# 1U_attenuvert_redesign.net
KiCad netlist of a schematic drawn in EAGLE
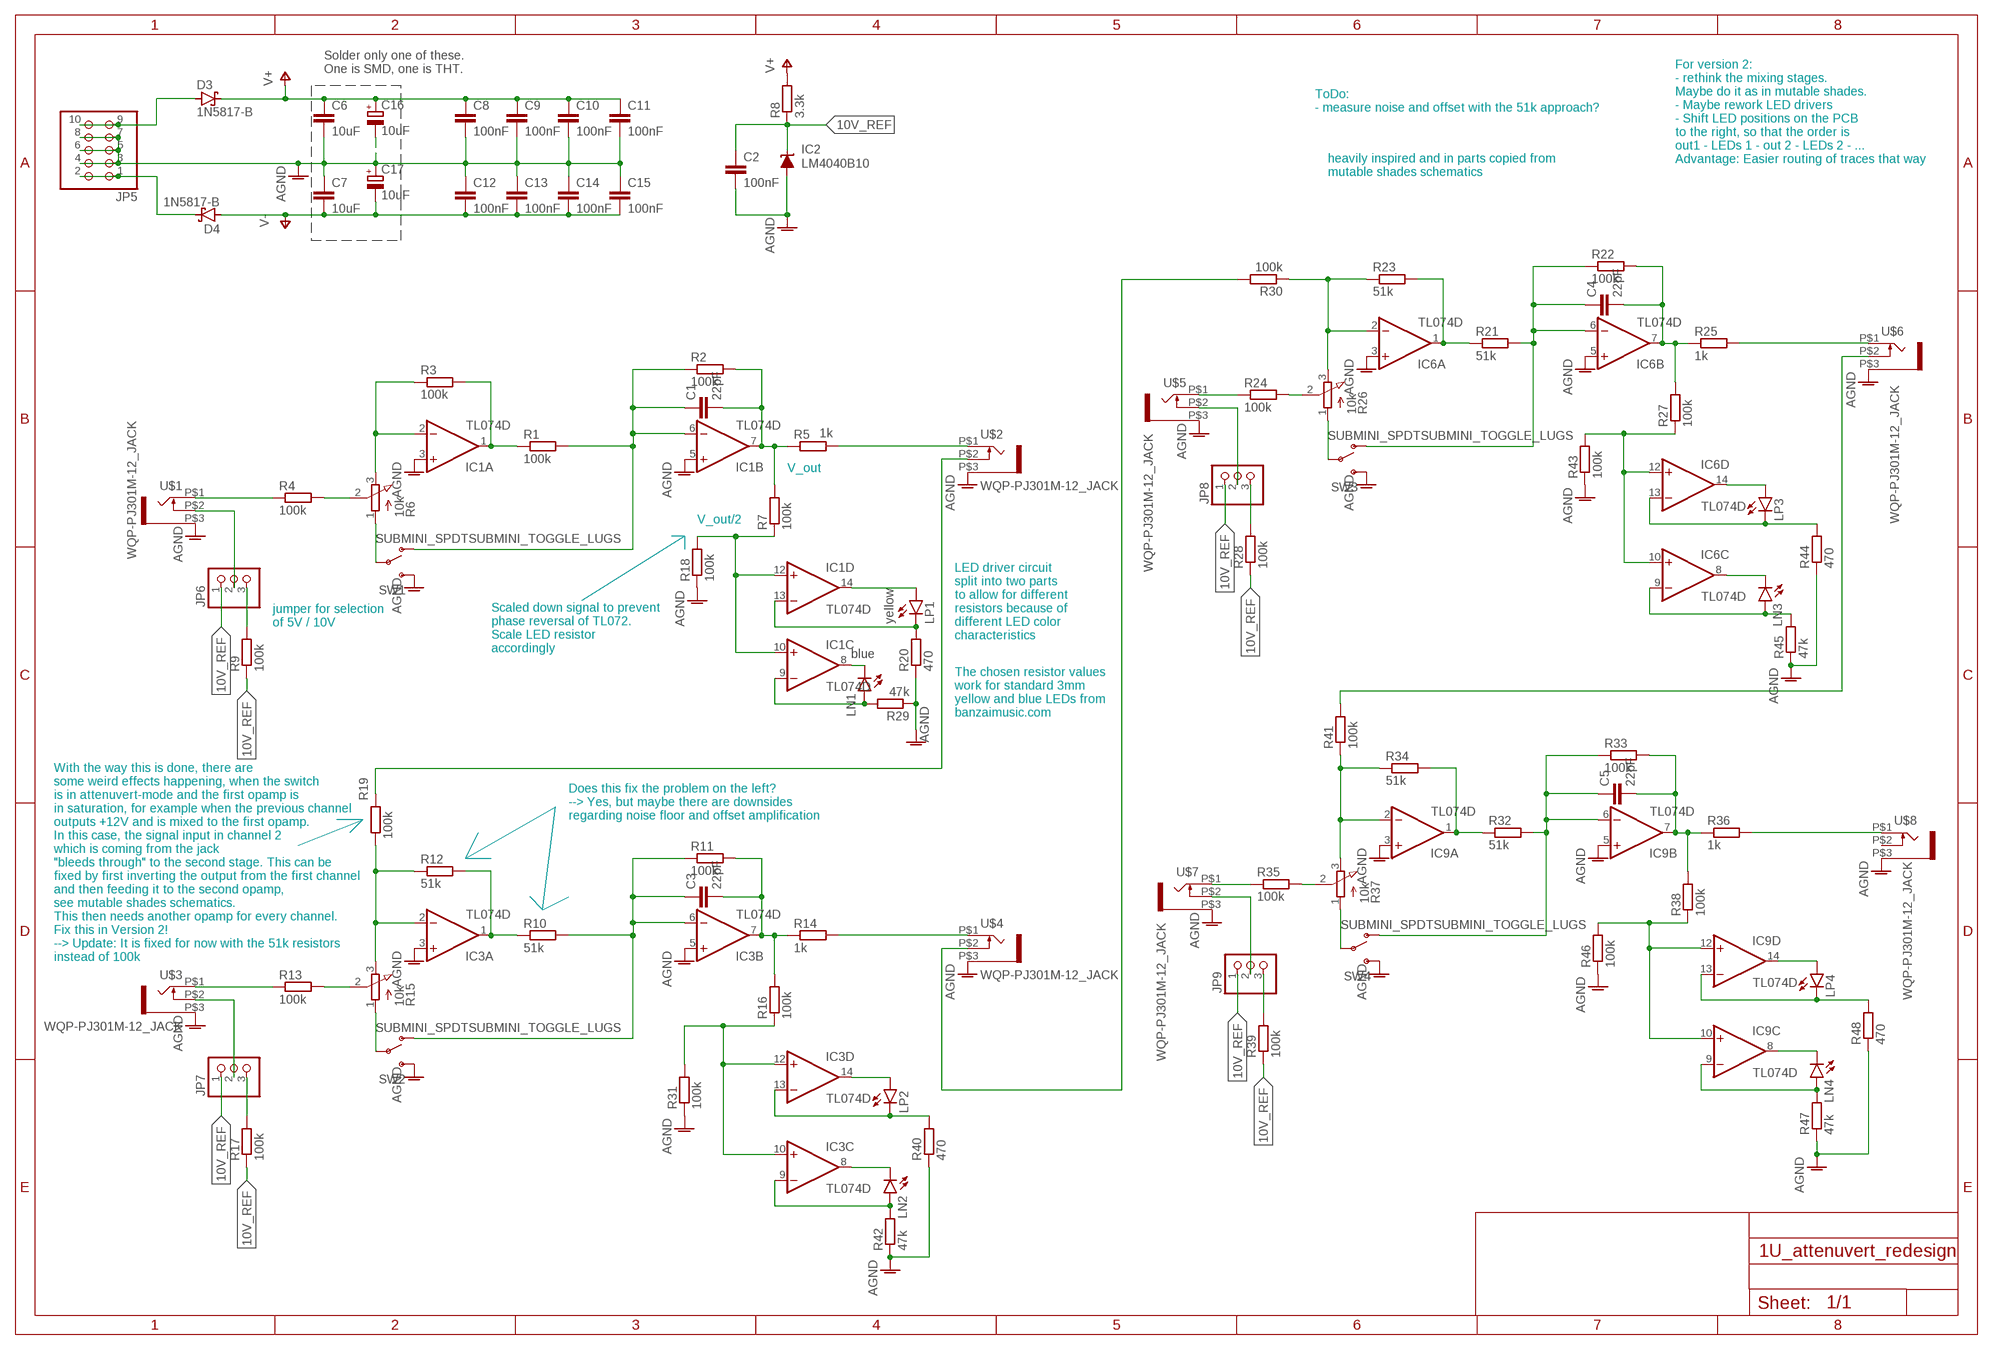
[diagram p0: schematic, sheet 1]

(export (version "E")
  (design (tool "Eeschema 10.0.6"))
  (components
    (comp (ref "C1")
      (value "22pF")
      (footprint "eagle-import:C0603")
      (libsource (lib "eagle-import") (part "C-EUC0603"))
    )
    (comp (ref "C2")
      (value "100nF")
      (footprint "eagle-import:C0603")
      (libsource (lib "eagle-import") (part "C-EUC0603"))
    )
    (comp (ref "C3")
      (value "22pF")
      (footprint "eagle-import:C0603")
      (libsource (lib "eagle-import") (part "C-EUC0603"))
    )
    (comp (ref "C4")
      (value "22pF")
      (footprint "eagle-import:C0603")
      (libsource (lib "eagle-import") (part "C-EUC0603"))
    )
    (comp (ref "C5")
      (value "22pF")
      (footprint "eagle-import:C0603")
      (libsource (lib "eagle-import") (part "C-EUC0603"))
    )
    (comp (ref "C6")
      (value "10uF")
      (footprint "eagle-import:C0805")
      (libsource (lib "eagle-import") (part "C-EUC0805"))
    )
    (comp (ref "C7")
      (value "10uF")
      (footprint "eagle-import:C0805")
      (libsource (lib "eagle-import") (part "C-EUC0805"))
    )
    (comp (ref "C8")
      (value "100nF")
      (footprint "eagle-import:C0603")
      (libsource (lib "eagle-import") (part "C-EUC0603"))
    )
    (comp (ref "C9")
      (value "100nF")
      (footprint "eagle-import:C0603")
      (libsource (lib "eagle-import") (part "C-EUC0603"))
    )
    (comp (ref "C10")
      (value "100nF")
      (footprint "eagle-import:C0603")
      (libsource (lib "eagle-import") (part "C-EUC0603"))
    )
    (comp (ref "C11")
      (value "100nF")
      (footprint "eagle-import:C0603")
      (libsource (lib "eagle-import") (part "C-EUC0603"))
    )
    (comp (ref "C12")
      (value "100nF")
      (footprint "eagle-import:C0603")
      (libsource (lib "eagle-import") (part "C-EUC0603"))
    )
    (comp (ref "C13")
      (value "100nF")
      (footprint "eagle-import:C0603")
      (libsource (lib "eagle-import") (part "C-EUC0603"))
    )
    (comp (ref "C14")
      (value "100nF")
      (footprint "eagle-import:C0603")
      (libsource (lib "eagle-import") (part "C-EUC0603"))
    )
    (comp (ref "C15")
      (value "100nF")
      (footprint "eagle-import:C0603")
      (libsource (lib "eagle-import") (part "C-EUC0603"))
    )
    (comp (ref "C16")
      (value "10uF")
      (footprint "eagle-import:E2,5-6")
      (libsource (lib "eagle-import") (part "CPOL-EUE2.5-6"))
    )
    (comp (ref "C17")
      (value "10uF")
      (footprint "eagle-import:E2,5-6")
      (libsource (lib "eagle-import") (part "CPOL-EUE2.5-6"))
    )
    (comp (ref "D3")
      (value "1N5817-B")
      (footprint "eagle-import:DO41-7.6")
      (libsource (lib "eagle-import") (part "1N5817-B"))
    )
    (comp (ref "D4")
      (value "1N5817-B")
      (footprint "eagle-import:DO41-7.6")
      (libsource (lib "eagle-import") (part "1N5817-B"))
    )
    (comp (ref "IC1")
      (value "TL074D")
      (footprint "eagle-import:SO14")
      (libsource (lib "eagle-import") (part "TL074D"))
    )
    (comp (ref "IC2")
      (value "LM4040B10")
      (footprint "eagle-import:DBZ_R-PDSO-G3")
      (fields (field (name "MPN") "LM4041A12IDBZR"))
      (libsource (lib "eagle-import") (part "LM4041DBZA12"))
    )
    (comp (ref "IC3")
      (value "TL074D")
      (footprint "eagle-import:SO14")
      (libsource (lib "eagle-import") (part "TL074D"))
    )
    (comp (ref "IC6")
      (value "TL074D")
      (footprint "eagle-import:SO14")
      (libsource (lib "eagle-import") (part "TL074D"))
    )
    (comp (ref "IC9")
      (value "TL074D")
      (footprint "eagle-import:SO14")
      (libsource (lib "eagle-import") (part "TL074D"))
    )
    (comp (ref "JP5")
      (value "PINHD-2X5")
      (footprint "eagle-import:2X05")
      (libsource (lib "eagle-import") (part "PINHD-2X5"))
    )
    (comp (ref "JP6")
      (value "PINHD-1X3")
      (footprint "eagle-import:1X03")
      (libsource (lib "eagle-import") (part "PINHD-1X3"))
    )
    (comp (ref "JP7")
      (value "PINHD-1X3")
      (footprint "eagle-import:1X03")
      (libsource (lib "eagle-import") (part "PINHD-1X3"))
    )
    (comp (ref "JP8")
      (value "PINHD-1X3")
      (footprint "eagle-import:1X03")
      (libsource (lib "eagle-import") (part "PINHD-1X3"))
    )
    (comp (ref "JP9")
      (value "PINHD-1X3")
      (footprint "eagle-import:1X03")
      (libsource (lib "eagle-import") (part "PINHD-1X3"))
    )
    (comp (ref "LN1")
      (value "blue")
      (footprint "eagle-import:LED3MM")
      (libsource (lib "eagle-import") (part "LED3MM"))
    )
    (comp (ref "LN2")
      (value "LED3MM")
      (footprint "eagle-import:LED3MM")
      (libsource (lib "eagle-import") (part "LED3MM"))
    )
    (comp (ref "LN3")
      (value "LED3MM")
      (footprint "eagle-import:LED3MM")
      (libsource (lib "eagle-import") (part "LED3MM"))
    )
    (comp (ref "LN4")
      (value "LED3MM")
      (footprint "eagle-import:LED3MM")
      (libsource (lib "eagle-import") (part "LED3MM"))
    )
    (comp (ref "LP1")
      (value "yellow")
      (footprint "eagle-import:LED3MM")
      (libsource (lib "eagle-import") (part "LED3MM"))
    )
    (comp (ref "LP2")
      (value "LED3MM")
      (footprint "eagle-import:LED3MM")
      (libsource (lib "eagle-import") (part "LED3MM"))
    )
    (comp (ref "LP3")
      (value "LED3MM")
      (footprint "eagle-import:LED3MM")
      (libsource (lib "eagle-import") (part "LED3MM"))
    )
    (comp (ref "LP4")
      (value "LED3MM")
      (footprint "eagle-import:LED3MM")
      (libsource (lib "eagle-import") (part "LED3MM"))
    )
    (comp (ref "R1")
      (value "100k")
      (footprint "eagle-import:R0603")
      (libsource (lib "eagle-import") (part "R-EU_R0603"))
    )
    (comp (ref "R2")
      (value "100k")
      (footprint "eagle-import:R0603")
      (libsource (lib "eagle-import") (part "R-EU_R0603"))
    )
    (comp (ref "R3")
      (value "100k")
      (footprint "eagle-import:R0603")
      (libsource (lib "eagle-import") (part "R-EU_R0603"))
    )
    (comp (ref "R4")
      (value "100k")
      (footprint "eagle-import:R0603")
      (libsource (lib "eagle-import") (part "R-EU_R0603"))
    )
    (comp (ref "R5")
      (value "1k")
      (footprint "eagle-import:R0603")
      (libsource (lib "eagle-import") (part "R-EU_R0603"))
    )
    (comp (ref "R6")
      (value "10k")
      (footprint "eagle-import:EVUFXL")
      (libsource (lib "eagle-import") (part "EVULF2"))
    )
    (comp (ref "R7")
      (value "100k")
      (footprint "eagle-import:R0603")
      (libsource (lib "eagle-import") (part "R-EU_R0603"))
    )
    (comp (ref "R8")
      (value "3.3k")
      (footprint "eagle-import:R0603")
      (libsource (lib "eagle-import") (part "R-EU_R0603"))
    )
    (comp (ref "R9")
      (value "100k")
      (footprint "eagle-import:R0603")
      (libsource (lib "eagle-import") (part "R-EU_R0603"))
    )
    (comp (ref "R10")
      (value "51k")
      (footprint "eagle-import:R0603")
      (libsource (lib "eagle-import") (part "R-EU_R0603"))
    )
    (comp (ref "R11")
      (value "100k")
      (footprint "eagle-import:R0603")
      (libsource (lib "eagle-import") (part "R-EU_R0603"))
    )
    (comp (ref "R12")
      (value "51k")
      (footprint "eagle-import:R0603")
      (libsource (lib "eagle-import") (part "R-EU_R0603"))
    )
    (comp (ref "R13")
      (value "100k")
      (footprint "eagle-import:R0603")
      (libsource (lib "eagle-import") (part "R-EU_R0603"))
    )
    (comp (ref "R14")
      (value "1k")
      (footprint "eagle-import:R0603")
      (libsource (lib "eagle-import") (part "R-EU_R0603"))
    )
    (comp (ref "R15")
      (value "10k")
      (footprint "eagle-import:EVUFXL")
      (libsource (lib "eagle-import") (part "EVULF2"))
    )
    (comp (ref "R16")
      (value "100k")
      (footprint "eagle-import:R0603")
      (libsource (lib "eagle-import") (part "R-EU_R0603"))
    )
    (comp (ref "R17")
      (value "100k")
      (footprint "eagle-import:R0603")
      (libsource (lib "eagle-import") (part "R-EU_R0603"))
    )
    (comp (ref "R18")
      (value "100k")
      (footprint "eagle-import:R0603")
      (libsource (lib "eagle-import") (part "R-EU_R0603"))
    )
    (comp (ref "R19")
      (value "100k")
      (footprint "eagle-import:R0603")
      (libsource (lib "eagle-import") (part "R-EU_R0603"))
    )
    (comp (ref "R20")
      (value "470")
      (footprint "eagle-import:R0603")
      (libsource (lib "eagle-import") (part "R-EU_R0603"))
    )
    (comp (ref "R21")
      (value "51k")
      (footprint "eagle-import:R0603")
      (libsource (lib "eagle-import") (part "R-EU_R0603"))
    )
    (comp (ref "R22")
      (value "100k")
      (footprint "eagle-import:R0603")
      (libsource (lib "eagle-import") (part "R-EU_R0603"))
    )
    (comp (ref "R23")
      (value "51k")
      (footprint "eagle-import:R0603")
      (libsource (lib "eagle-import") (part "R-EU_R0603"))
    )
    (comp (ref "R24")
      (value "100k")
      (footprint "eagle-import:R0603")
      (libsource (lib "eagle-import") (part "R-EU_R0603"))
    )
    (comp (ref "R25")
      (value "1k")
      (footprint "eagle-import:R0603")
      (libsource (lib "eagle-import") (part "R-EU_R0603"))
    )
    (comp (ref "R26")
      (value "10k")
      (footprint "eagle-import:EVUFXL")
      (libsource (lib "eagle-import") (part "EVULF2"))
    )
    (comp (ref "R27")
      (value "100k")
      (footprint "eagle-import:R0603")
      (libsource (lib "eagle-import") (part "R-EU_R0603"))
    )
    (comp (ref "R28")
      (value "100k")
      (footprint "eagle-import:R0603")
      (libsource (lib "eagle-import") (part "R-EU_R0603"))
    )
    (comp (ref "R29")
      (value "47k")
      (footprint "eagle-import:R0603")
      (libsource (lib "eagle-import") (part "R-EU_R0603"))
    )
    (comp (ref "R30")
      (value "100k")
      (footprint "eagle-import:R0603")
      (libsource (lib "eagle-import") (part "R-EU_R0603"))
    )
    (comp (ref "R31")
      (value "100k")
      (footprint "eagle-import:R0603")
      (libsource (lib "eagle-import") (part "R-EU_R0603"))
    )
    (comp (ref "R32")
      (value "51k")
      (footprint "eagle-import:R0603")
      (libsource (lib "eagle-import") (part "R-EU_R0603"))
    )
    (comp (ref "R33")
      (value "100k")
      (footprint "eagle-import:R0603")
      (libsource (lib "eagle-import") (part "R-EU_R0603"))
    )
    (comp (ref "R34")
      (value "51k")
      (footprint "eagle-import:R0603")
      (libsource (lib "eagle-import") (part "R-EU_R0603"))
    )
    (comp (ref "R35")
      (value "100k")
      (footprint "eagle-import:R0603")
      (libsource (lib "eagle-import") (part "R-EU_R0603"))
    )
    (comp (ref "R36")
      (value "1k")
      (footprint "eagle-import:R0603")
      (libsource (lib "eagle-import") (part "R-EU_R0603"))
    )
    (comp (ref "R37")
      (value "10k")
      (footprint "eagle-import:EVUFXL")
      (libsource (lib "eagle-import") (part "EVULF2"))
    )
    (comp (ref "R38")
      (value "100k")
      (footprint "eagle-import:R0603")
      (libsource (lib "eagle-import") (part "R-EU_R0603"))
    )
    (comp (ref "R39")
      (value "100k")
      (footprint "eagle-import:R0603")
      (libsource (lib "eagle-import") (part "R-EU_R0603"))
    )
    (comp (ref "R40")
      (value "470")
      (footprint "eagle-import:R0603")
      (libsource (lib "eagle-import") (part "R-EU_R0603"))
    )
    (comp (ref "R41")
      (value "100k")
      (footprint "eagle-import:R0603")
      (libsource (lib "eagle-import") (part "R-EU_R0603"))
    )
    (comp (ref "R42")
      (value "47k")
      (footprint "eagle-import:R0603")
      (libsource (lib "eagle-import") (part "R-EU_R0603"))
    )
    (comp (ref "R43")
      (value "100k")
      (footprint "eagle-import:R0603")
      (libsource (lib "eagle-import") (part "R-EU_R0603"))
    )
    (comp (ref "R44")
      (value "470")
      (footprint "eagle-import:R0603")
      (libsource (lib "eagle-import") (part "R-EU_R0603"))
    )
    (comp (ref "R45")
      (value "47k")
      (footprint "eagle-import:R0603")
      (libsource (lib "eagle-import") (part "R-EU_R0603"))
    )
    (comp (ref "R46")
      (value "100k")
      (footprint "eagle-import:R0603")
      (libsource (lib "eagle-import") (part "R-EU_R0603"))
    )
    (comp (ref "R47")
      (value "47k")
      (footprint "eagle-import:R0603")
      (libsource (lib "eagle-import") (part "R-EU_R0603"))
    )
    (comp (ref "R48")
      (value "470")
      (footprint "eagle-import:R0603")
      (libsource (lib "eagle-import") (part "R-EU_R0603"))
    )
    (comp (ref "SW1")
      (value "SUBMINI_SPDTSUBMINI_TOGGLE_LUGS")
      (footprint "eagle-import:SUBMINI_TOGGLE_LUGS")
      (libsource (lib "eagle-import") (part "SUBMINI_SPDTSUBMINI_TOGGLE_LUGS"))
    )
    (comp (ref "SW2")
      (value "SUBMINI_SPDTSUBMINI_TOGGLE_LUGS")
      (footprint "eagle-import:SUBMINI_TOGGLE_LUGS")
      (libsource (lib "eagle-import") (part "SUBMINI_SPDTSUBMINI_TOGGLE_LUGS"))
    )
    (comp (ref "SW3")
      (value "SUBMINI_SPDTSUBMINI_TOGGLE_LUGS")
      (footprint "eagle-import:SUBMINI_TOGGLE_LUGS")
      (libsource (lib "eagle-import") (part "SUBMINI_SPDTSUBMINI_TOGGLE_LUGS"))
    )
    (comp (ref "SW4")
      (value "SUBMINI_SPDTSUBMINI_TOGGLE_LUGS")
      (footprint "eagle-import:SUBMINI_TOGGLE_LUGS")
      (libsource (lib "eagle-import") (part "SUBMINI_SPDTSUBMINI_TOGGLE_LUGS"))
    )
    (comp (ref "U$1")
      (value "WQP-PJ301M-12_JACK")
      (footprint "eagle-import:WQP-PJ301M-12_JACK")
      (libsource (lib "eagle-import") (part "WQP-PJ301M-12_JACK"))
    )
    (comp (ref "U$2")
      (value "WQP-PJ301M-12_JACK")
      (footprint "eagle-import:WQP-PJ301M-12_JACK")
      (libsource (lib "eagle-import") (part "WQP-PJ301M-12_JACK"))
    )
    (comp (ref "U$3")
      (value "WQP-PJ301M-12_JACK")
      (footprint "eagle-import:WQP-PJ301M-12_JACK")
      (libsource (lib "eagle-import") (part "WQP-PJ301M-12_JACK"))
    )
    (comp (ref "U$4")
      (value "WQP-PJ301M-12_JACK")
      (footprint "eagle-import:WQP-PJ301M-12_JACK")
      (libsource (lib "eagle-import") (part "WQP-PJ301M-12_JACK"))
    )
    (comp (ref "U$5")
      (value "WQP-PJ301M-12_JACK")
      (footprint "eagle-import:WQP-PJ301M-12_JACK")
      (libsource (lib "eagle-import") (part "WQP-PJ301M-12_JACK"))
    )
    (comp (ref "U$6")
      (value "WQP-PJ301M-12_JACK")
      (footprint "eagle-import:WQP-PJ301M-12_JACK")
      (libsource (lib "eagle-import") (part "WQP-PJ301M-12_JACK"))
    )
    (comp (ref "U$7")
      (value "WQP-PJ301M-12_JACK")
      (footprint "eagle-import:WQP-PJ301M-12_JACK")
      (libsource (lib "eagle-import") (part "WQP-PJ301M-12_JACK"))
    )
    (comp (ref "U$8")
      (value "WQP-PJ301M-12_JACK")
      (footprint "eagle-import:WQP-PJ301M-12_JACK")
      (libsource (lib "eagle-import") (part "WQP-PJ301M-12_JACK"))
    )
  )
  (nets
    (net (code "1") (name "10V_REF") (class "Default")
      (node (ref "C2") (pin "1") (pinfunction "1_1") (pintype "passive"))
      (node (ref "IC2") (pin "1") (pinfunction "C_1") (pintype "passive"))
      (node (ref "JP6") (pin "1") (pinfunction "1_1") (pintype "passive"))
      (node (ref "JP7") (pin "1") (pinfunction "1_1") (pintype "passive"))
      (node (ref "JP8") (pin "1") (pinfunction "1_1") (pintype "passive"))
      (node (ref "JP9") (pin "1") (pinfunction "1_1") (pintype "passive"))
      (node (ref "R17") (pin "1") (pinfunction "1_1") (pintype "passive"))
      (node (ref "R28") (pin "1") (pinfunction "1_1") (pintype "passive"))
      (node (ref "R39") (pin "1") (pinfunction "1_1") (pintype "passive"))
      (node (ref "R8") (pin "1") (pinfunction "1_1") (pintype "passive"))
      (node (ref "R9") (pin "1") (pinfunction "1_1") (pintype "passive"))
    )
    (net (code "2") (name "AGND") (class "Default")
      (node (ref "C10") (pin "2") (pinfunction "2_2") (pintype "passive"))
      (node (ref "C11") (pin "2") (pinfunction "2_2") (pintype "passive"))
      (node (ref "C12") (pin "1") (pinfunction "1_1") (pintype "passive"))
      (node (ref "C13") (pin "1") (pinfunction "1_1") (pintype "passive"))
      (node (ref "C14") (pin "1") (pinfunction "1_1") (pintype "passive"))
      (node (ref "C15") (pin "1") (pinfunction "1_1") (pintype "passive"))
      (node (ref "C16") (pin "-") (pinfunction "-_-") (pintype "passive"))
      (node (ref "C17") (pin "+") (pinfunction "+_+") (pintype "passive"))
      (node (ref "C2") (pin "2") (pinfunction "2_2") (pintype "passive"))
      (node (ref "C6") (pin "2") (pinfunction "2_2") (pintype "passive"))
      (node (ref "C7") (pin "1") (pinfunction "1_1") (pintype "passive"))
      (node (ref "C8") (pin "2") (pinfunction "2_2") (pintype "passive"))
      (node (ref "C9") (pin "2") (pinfunction "2_2") (pintype "passive"))
      (node (ref "IC1") (pin "3") (pinfunction "+IN_3") (pintype "input"))
      (node (ref "IC1") (pin "5") (pinfunction "+IN_5") (pintype "input"))
      (node (ref "IC2") (pin "2") (pinfunction "A_2") (pintype "passive"))
      (node (ref "IC3") (pin "3") (pinfunction "+IN_3") (pintype "input"))
      (node (ref "IC3") (pin "5") (pinfunction "+IN_5") (pintype "input"))
      (node (ref "IC6") (pin "3") (pinfunction "+IN_3") (pintype "input"))
      (node (ref "IC6") (pin "5") (pinfunction "+IN_5") (pintype "input"))
      (node (ref "IC9") (pin "3") (pinfunction "+IN_3") (pintype "input"))
      (node (ref "IC9") (pin "5") (pinfunction "+IN_5") (pintype "input"))
      (node (ref "JP5") (pin "3") (pinfunction "3_3") (pintype "passive"))
      (node (ref "JP5") (pin "4") (pinfunction "4_4") (pintype "passive"))
      (node (ref "JP5") (pin "5") (pinfunction "5_5") (pintype "passive"))
      (node (ref "JP5") (pin "6") (pinfunction "6_6") (pintype "passive"))
      (node (ref "JP5") (pin "7") (pinfunction "7_7") (pintype "passive"))
      (node (ref "JP5") (pin "8") (pinfunction "8_8") (pintype "passive"))
      (node (ref "R18") (pin "1") (pinfunction "1_1") (pintype "passive"))
      (node (ref "R20") (pin "1") (pinfunction "1_1") (pintype "passive"))
      (node (ref "R29") (pin "1") (pinfunction "1_1") (pintype "passive"))
      (node (ref "R31") (pin "1") (pinfunction "1_1") (pintype "passive"))
      (node (ref "R40") (pin "1") (pinfunction "1_1") (pintype "passive"))
      (node (ref "R42") (pin "1") (pinfunction "1_1") (pintype "passive"))
      (node (ref "R43") (pin "1") (pinfunction "1_1") (pintype "passive"))
      (node (ref "R44") (pin "1") (pinfunction "1_1") (pintype "passive"))
      (node (ref "R45") (pin "1") (pinfunction "1_1") (pintype "passive"))
      (node (ref "R46") (pin "1") (pinfunction "1_1") (pintype "passive"))
      (node (ref "R47") (pin "1") (pinfunction "1_1") (pintype "passive"))
      (node (ref "R48") (pin "1") (pinfunction "1_1") (pintype "passive"))
      (node (ref "SW1") (pin "3") (pinfunction "S_3") (pintype "passive"))
      (node (ref "SW2") (pin "3") (pinfunction "S_3") (pintype "passive"))
      (node (ref "SW3") (pin "3") (pinfunction "S_3") (pintype "passive"))
      (node (ref "SW4") (pin "3") (pinfunction "S_3") (pintype "passive"))
      (node (ref "U$1") (pin "P$3") (pinfunction "1_P$3") (pintype "passive"))
      (node (ref "U$2") (pin "P$3") (pinfunction "1_P$3") (pintype "passive"))
      (node (ref "U$3") (pin "P$3") (pinfunction "1_P$3") (pintype "passive"))
      (node (ref "U$4") (pin "P$3") (pinfunction "1_P$3") (pintype "passive"))
      (node (ref "U$5") (pin "P$3") (pinfunction "1_P$3") (pintype "passive"))
      (node (ref "U$6") (pin "P$3") (pinfunction "1_P$3") (pintype "passive"))
      (node (ref "U$7") (pin "P$3") (pinfunction "1_P$3") (pintype "passive"))
      (node (ref "U$8") (pin "P$3") (pinfunction "1_P$3") (pintype "passive"))
    )
    (net (code "3") (name "Net-(D3-PadA)") (class "Default")
      (node (ref "D3") (pin "A") (pinfunction "A_A") (pintype "passive"))
      (node (ref "JP5") (pin "10") (pinfunction "10_10") (pintype "passive"))
      (node (ref "JP5") (pin "9") (pinfunction "9_9") (pintype "passive"))
    )
    (net (code "4") (name "Net-(D4-PadC)") (class "Default")
      (node (ref "D4") (pin "C") (pinfunction "C_C") (pintype "passive"))
      (node (ref "JP5") (pin "1") (pinfunction "1_1") (pintype "passive"))
      (node (ref "JP5") (pin "2") (pinfunction "2_2") (pintype "passive"))
    )
    (net (code "5") (name "Net-(IC1A--IN)") (class "Default")
      (node (ref "IC1") (pin "2") (pinfunction "-IN_2") (pintype "input"))
      (node (ref "R3") (pin "1") (pinfunction "1_1") (pintype "passive"))
      (node (ref "R6") (pin "3") (pinfunction "E_3") (pintype "passive"))
    )
    (net (code "6") (name "Net-(IC1A-OUT)") (class "Default")
      (node (ref "IC1") (pin "1") (pinfunction "OUT_1") (pintype "output"))
      (node (ref "R1") (pin "1") (pinfunction "1_1") (pintype "passive"))
      (node (ref "R3") (pin "2") (pinfunction "2_2") (pintype "passive"))
    )
    (net (code "7") (name "Net-(IC1B--IN)") (class "Default")
      (node (ref "C1") (pin "1") (pinfunction "1_1") (pintype "passive"))
      (node (ref "IC1") (pin "6") (pinfunction "-IN_6") (pintype "input"))
      (node (ref "R1") (pin "2") (pinfunction "2_2") (pintype "passive"))
      (node (ref "R2") (pin "1") (pinfunction "1_1") (pintype "passive"))
      (node (ref "SW1") (pin "1") (pinfunction "O_1") (pintype "passive"))
    )
    (net (code "8") (name "Net-(IC1B-OUT)") (class "Default")
      (node (ref "C1") (pin "2") (pinfunction "2_2") (pintype "passive"))
      (node (ref "IC1") (pin "7") (pinfunction "OUT_7") (pintype "output"))
      (node (ref "R2") (pin "2") (pinfunction "2_2") (pintype "passive"))
      (node (ref "R5") (pin "1") (pinfunction "1_1") (pintype "passive"))
      (node (ref "R7") (pin "2") (pinfunction "2_2") (pintype "passive"))
    )
    (net (code "9") (name "Net-(IC1C-+IN)") (class "Default")
      (node (ref "IC1") (pin "10") (pinfunction "+IN_10") (pintype "input"))
      (node (ref "IC1") (pin "12") (pinfunction "+IN_12") (pintype "input"))
      (node (ref "R18") (pin "2") (pinfunction "2_2") (pintype "passive"))
      (node (ref "R7") (pin "1") (pinfunction "1_1") (pintype "passive"))
    )
    (net (code "10") (name "Net-(IC1C--IN)") (class "Default")
      (node (ref "IC1") (pin "9") (pinfunction "-IN_9") (pintype "input"))
      (node (ref "LN1") (pin "A") (pinfunction "A_A") (pintype "passive"))
      (node (ref "R29") (pin "2") (pinfunction "2_2") (pintype "passive"))
    )
    (net (code "11") (name "Net-(IC1C-OUT)") (class "Default")
      (node (ref "IC1") (pin "8") (pinfunction "OUT_8") (pintype "output"))
      (node (ref "LN1") (pin "K") (pinfunction "C_K") (pintype "passive"))
    )
    (net (code "12") (name "Net-(IC1D--IN)") (class "Default")
      (node (ref "IC1") (pin "13") (pinfunction "-IN_13") (pintype "input"))
      (node (ref "LP1") (pin "K") (pinfunction "C_K") (pintype "passive"))
      (node (ref "R20") (pin "2") (pinfunction "2_2") (pintype "passive"))
    )
    (net (code "13") (name "Net-(IC1D-OUT)") (class "Default")
      (node (ref "IC1") (pin "14") (pinfunction "OUT_14") (pintype "output"))
      (node (ref "LP1") (pin "A") (pinfunction "A_A") (pintype "passive"))
    )
    (net (code "14") (name "Net-(IC3A--IN)") (class "Default")
      (node (ref "IC3") (pin "2") (pinfunction "-IN_2") (pintype "input"))
      (node (ref "R12") (pin "1") (pinfunction "1_1") (pintype "passive"))
      (node (ref "R15") (pin "3") (pinfunction "E_3") (pintype "passive"))
      (node (ref "R19") (pin "1") (pinfunction "1_1") (pintype "passive"))
    )
    (net (code "15") (name "Net-(IC3A-OUT)") (class "Default")
      (node (ref "IC3") (pin "1") (pinfunction "OUT_1") (pintype "output"))
      (node (ref "R10") (pin "1") (pinfunction "1_1") (pintype "passive"))
      (node (ref "R12") (pin "2") (pinfunction "2_2") (pintype "passive"))
    )
    (net (code "16") (name "Net-(IC3B--IN)") (class "Default")
      (node (ref "C3") (pin "1") (pinfunction "1_1") (pintype "passive"))
      (node (ref "IC3") (pin "6") (pinfunction "-IN_6") (pintype "input"))
      (node (ref "R10") (pin "2") (pinfunction "2_2") (pintype "passive"))
      (node (ref "R11") (pin "1") (pinfunction "1_1") (pintype "passive"))
      (node (ref "SW2") (pin "1") (pinfunction "O_1") (pintype "passive"))
    )
    (net (code "17") (name "Net-(IC3B-OUT)") (class "Default")
      (node (ref "C3") (pin "2") (pinfunction "2_2") (pintype "passive"))
      (node (ref "IC3") (pin "7") (pinfunction "OUT_7") (pintype "output"))
      (node (ref "R11") (pin "2") (pinfunction "2_2") (pintype "passive"))
      (node (ref "R14") (pin "1") (pinfunction "1_1") (pintype "passive"))
      (node (ref "R16") (pin "2") (pinfunction "2_2") (pintype "passive"))
    )
    (net (code "18") (name "Net-(IC3C-+IN)") (class "Default")
      (node (ref "IC3") (pin "10") (pinfunction "+IN_10") (pintype "input"))
      (node (ref "IC3") (pin "12") (pinfunction "+IN_12") (pintype "input"))
      (node (ref "R16") (pin "1") (pinfunction "1_1") (pintype "passive"))
      (node (ref "R31") (pin "2") (pinfunction "2_2") (pintype "passive"))
    )
    (net (code "19") (name "Net-(IC3C--IN)") (class "Default")
      (node (ref "IC3") (pin "9") (pinfunction "-IN_9") (pintype "input"))
      (node (ref "LN2") (pin "A") (pinfunction "A_A") (pintype "passive"))
      (node (ref "R42") (pin "2") (pinfunction "2_2") (pintype "passive"))
    )
    (net (code "20") (name "Net-(IC3C-OUT)") (class "Default")
      (node (ref "IC3") (pin "8") (pinfunction "OUT_8") (pintype "output"))
      (node (ref "LN2") (pin "K") (pinfunction "C_K") (pintype "passive"))
    )
    (net (code "21") (name "Net-(IC3D--IN)") (class "Default")
      (node (ref "IC3") (pin "13") (pinfunction "-IN_13") (pintype "input"))
      (node (ref "LP2") (pin "K") (pinfunction "C_K") (pintype "passive"))
      (node (ref "R40") (pin "2") (pinfunction "2_2") (pintype "passive"))
    )
    (net (code "22") (name "Net-(IC3D-OUT)") (class "Default")
      (node (ref "IC3") (pin "14") (pinfunction "OUT_14") (pintype "output"))
      (node (ref "LP2") (pin "A") (pinfunction "A_A") (pintype "passive"))
    )
    (net (code "23") (name "Net-(IC6A--IN)") (class "Default")
      (node (ref "IC6") (pin "2") (pinfunction "-IN_2") (pintype "input"))
      (node (ref "R23") (pin "1") (pinfunction "1_1") (pintype "passive"))
      (node (ref "R26") (pin "3") (pinfunction "E_3") (pintype "passive"))
      (node (ref "R30") (pin "1") (pinfunction "1_1") (pintype "passive"))
    )
    (net (code "24") (name "Net-(IC6A-OUT)") (class "Default")
      (node (ref "IC6") (pin "1") (pinfunction "OUT_1") (pintype "output"))
      (node (ref "R21") (pin "1") (pinfunction "1_1") (pintype "passive"))
      (node (ref "R23") (pin "2") (pinfunction "2_2") (pintype "passive"))
    )
    (net (code "25") (name "Net-(IC6B--IN)") (class "Default")
      (node (ref "C4") (pin "1") (pinfunction "1_1") (pintype "passive"))
      (node (ref "IC6") (pin "6") (pinfunction "-IN_6") (pintype "input"))
      (node (ref "R21") (pin "2") (pinfunction "2_2") (pintype "passive"))
      (node (ref "R22") (pin "1") (pinfunction "1_1") (pintype "passive"))
      (node (ref "SW3") (pin "1") (pinfunction "O_1") (pintype "passive"))
    )
    (net (code "26") (name "Net-(IC6B-OUT)") (class "Default")
      (node (ref "C4") (pin "2") (pinfunction "2_2") (pintype "passive"))
      (node (ref "IC6") (pin "7") (pinfunction "OUT_7") (pintype "output"))
      (node (ref "R22") (pin "2") (pinfunction "2_2") (pintype "passive"))
      (node (ref "R25") (pin "1") (pinfunction "1_1") (pintype "passive"))
      (node (ref "R27") (pin "2") (pinfunction "2_2") (pintype "passive"))
    )
    (net (code "27") (name "Net-(IC6C-+IN)") (class "Default")
      (node (ref "IC6") (pin "10") (pinfunction "+IN_10") (pintype "input"))
      (node (ref "IC6") (pin "12") (pinfunction "+IN_12") (pintype "input"))
      (node (ref "R27") (pin "1") (pinfunction "1_1") (pintype "passive"))
      (node (ref "R43") (pin "2") (pinfunction "2_2") (pintype "passive"))
    )
    (net (code "28") (name "Net-(IC6C--IN)") (class "Default")
      (node (ref "IC6") (pin "9") (pinfunction "-IN_9") (pintype "input"))
      (node (ref "LN3") (pin "A") (pinfunction "A_A") (pintype "passive"))
      (node (ref "R45") (pin "2") (pinfunction "2_2") (pintype "passive"))
    )
    (net (code "29") (name "Net-(IC6C-OUT)") (class "Default")
      (node (ref "IC6") (pin "8") (pinfunction "OUT_8") (pintype "output"))
      (node (ref "LN3") (pin "K") (pinfunction "C_K") (pintype "passive"))
    )
    (net (code "30") (name "Net-(IC6D--IN)") (class "Default")
      (node (ref "IC6") (pin "13") (pinfunction "-IN_13") (pintype "input"))
      (node (ref "LP3") (pin "K") (pinfunction "C_K") (pintype "passive"))
      (node (ref "R44") (pin "2") (pinfunction "2_2") (pintype "passive"))
    )
    (net (code "31") (name "Net-(IC6D-OUT)") (class "Default")
      (node (ref "IC6") (pin "14") (pinfunction "OUT_14") (pintype "output"))
      (node (ref "LP3") (pin "A") (pinfunction "A_A") (pintype "passive"))
    )
    (net (code "32") (name "Net-(IC9A--IN)") (class "Default")
      (node (ref "IC9") (pin "2") (pinfunction "-IN_2") (pintype "input"))
      (node (ref "R34") (pin "1") (pinfunction "1_1") (pintype "passive"))
      (node (ref "R37") (pin "3") (pinfunction "E_3") (pintype "passive"))
      (node (ref "R41") (pin "1") (pinfunction "1_1") (pintype "passive"))
    )
    (net (code "33") (name "Net-(IC9A-OUT)") (class "Default")
      (node (ref "IC9") (pin "1") (pinfunction "OUT_1") (pintype "output"))
      (node (ref "R32") (pin "1") (pinfunction "1_1") (pintype "passive"))
      (node (ref "R34") (pin "2") (pinfunction "2_2") (pintype "passive"))
    )
    (net (code "34") (name "Net-(IC9B--IN)") (class "Default")
      (node (ref "C5") (pin "1") (pinfunction "1_1") (pintype "passive"))
      (node (ref "IC9") (pin "6") (pinfunction "-IN_6") (pintype "input"))
      (node (ref "R32") (pin "2") (pinfunction "2_2") (pintype "passive"))
      (node (ref "R33") (pin "1") (pinfunction "1_1") (pintype "passive"))
      (node (ref "SW4") (pin "1") (pinfunction "O_1") (pintype "passive"))
    )
    (net (code "35") (name "Net-(IC9B-OUT)") (class "Default")
      (node (ref "C5") (pin "2") (pinfunction "2_2") (pintype "passive"))
      (node (ref "IC9") (pin "7") (pinfunction "OUT_7") (pintype "output"))
      (node (ref "R33") (pin "2") (pinfunction "2_2") (pintype "passive"))
      (node (ref "R36") (pin "1") (pinfunction "1_1") (pintype "passive"))
      (node (ref "R38") (pin "2") (pinfunction "2_2") (pintype "passive"))
    )
    (net (code "36") (name "Net-(IC9C-+IN)") (class "Default")
      (node (ref "IC9") (pin "10") (pinfunction "+IN_10") (pintype "input"))
      (node (ref "IC9") (pin "12") (pinfunction "+IN_12") (pintype "input"))
      (node (ref "R38") (pin "1") (pinfunction "1_1") (pintype "passive"))
      (node (ref "R46") (pin "2") (pinfunction "2_2") (pintype "passive"))
    )
    (net (code "37") (name "Net-(IC9C--IN)") (class "Default")
      (node (ref "IC9") (pin "9") (pinfunction "-IN_9") (pintype "input"))
      (node (ref "LN4") (pin "A") (pinfunction "A_A") (pintype "passive"))
      (node (ref "R47") (pin "2") (pinfunction "2_2") (pintype "passive"))
    )
    (net (code "38") (name "Net-(IC9C-OUT)") (class "Default")
      (node (ref "IC9") (pin "8") (pinfunction "OUT_8") (pintype "output"))
      (node (ref "LN4") (pin "K") (pinfunction "C_K") (pintype "passive"))
    )
    (net (code "39") (name "Net-(IC9D--IN)") (class "Default")
      (node (ref "IC9") (pin "13") (pinfunction "-IN_13") (pintype "input"))
      (node (ref "LP4") (pin "K") (pinfunction "C_K") (pintype "passive"))
      (node (ref "R48") (pin "2") (pinfunction "2_2") (pintype "passive"))
    )
    (net (code "40") (name "Net-(IC9D-OUT)") (class "Default")
      (node (ref "IC9") (pin "14") (pinfunction "OUT_14") (pintype "output"))
      (node (ref "LP4") (pin "A") (pinfunction "A_A") (pintype "passive"))
    )
    (net (code "41") (name "Net-(JP6-Pad3)") (class "Default")
      (node (ref "JP6") (pin "3") (pinfunction "3_3") (pintype "passive"))
      (node (ref "R9") (pin "2") (pinfunction "2_2") (pintype "passive"))
    )
    (net (code "42") (name "Net-(JP7-Pad3)") (class "Default")
      (node (ref "JP7") (pin "3") (pinfunction "3_3") (pintype "passive"))
      (node (ref "R17") (pin "2") (pinfunction "2_2") (pintype "passive"))
    )
    (net (code "43") (name "Net-(JP8-Pad3)") (class "Default")
      (node (ref "JP8") (pin "3") (pinfunction "3_3") (pintype "passive"))
      (node (ref "R28") (pin "2") (pinfunction "2_2") (pintype "passive"))
    )
    (net (code "44") (name "Net-(JP9-Pad3)") (class "Default")
      (node (ref "JP9") (pin "3") (pinfunction "3_3") (pintype "passive"))
      (node (ref "R39") (pin "2") (pinfunction "2_2") (pintype "passive"))
    )
    (net (code "45") (name "Net-(R6-A)") (class "Default")
      (node (ref "R6") (pin "1") (pinfunction "A_1") (pintype "passive"))
      (node (ref "SW1") (pin "COM") (pinfunction "COMMON_COM") (pintype "passive"))
    )
    (net (code "46") (name "Net-(R6-S)") (class "Default")
      (node (ref "R4") (pin "2") (pinfunction "2_2") (pintype "passive"))
      (node (ref "R6") (pin "2") (pinfunction "S_2") (pintype "passive"))
    )
    (net (code "47") (name "Net-(R15-A)") (class "Default")
      (node (ref "R15") (pin "1") (pinfunction "A_1") (pintype "passive"))
      (node (ref "SW2") (pin "COM") (pinfunction "COMMON_COM") (pintype "passive"))
    )
    (net (code "48") (name "Net-(R15-S)") (class "Default")
      (node (ref "R13") (pin "2") (pinfunction "2_2") (pintype "passive"))
      (node (ref "R15") (pin "2") (pinfunction "S_2") (pintype "passive"))
    )
    (net (code "49") (name "Net-(R26-A)") (class "Default")
      (node (ref "R26") (pin "1") (pinfunction "A_1") (pintype "passive"))
      (node (ref "SW3") (pin "COM") (pinfunction "COMMON_COM") (pintype "passive"))
    )
    (net (code "50") (name "Net-(R26-S)") (class "Default")
      (node (ref "R24") (pin "2") (pinfunction "2_2") (pintype "passive"))
      (node (ref "R26") (pin "2") (pinfunction "S_2") (pintype "passive"))
    )
    (net (code "51") (name "Net-(R37-A)") (class "Default")
      (node (ref "R37") (pin "1") (pinfunction "A_1") (pintype "passive"))
      (node (ref "SW4") (pin "COM") (pinfunction "COMMON_COM") (pintype "passive"))
    )
    (net (code "52") (name "Net-(R37-S)") (class "Default")
      (node (ref "R35") (pin "2") (pinfunction "2_2") (pintype "passive"))
      (node (ref "R37") (pin "2") (pinfunction "S_2") (pintype "passive"))
    )
    (net (code "53") (name "Net-(U$1-2)") (class "Default")
      (node (ref "R4") (pin "1") (pinfunction "1_1") (pintype "passive"))
      (node (ref "U$1") (pin "P$1") (pinfunction "2_P$1") (pintype "passive"))
    )
    (net (code "54") (name "Net-(U$1-3)") (class "Default")
      (node (ref "JP6") (pin "2") (pinfunction "2_2") (pintype "passive"))
      (node (ref "U$1") (pin "P$2") (pinfunction "3_P$2") (pintype "passive"))
    )
    (net (code "55") (name "Net-(U$2-2)") (class "Default")
      (node (ref "R5") (pin "2") (pinfunction "2_2") (pintype "passive"))
      (node (ref "U$2") (pin "P$1") (pinfunction "2_P$1") (pintype "passive"))
    )
    (net (code "56") (name "Net-(U$2-3)") (class "Default")
      (node (ref "R19") (pin "2") (pinfunction "2_2") (pintype "passive"))
      (node (ref "U$2") (pin "P$2") (pinfunction "3_P$2") (pintype "passive"))
    )
    (net (code "57") (name "Net-(U$3-2)") (class "Default")
      (node (ref "R13") (pin "1") (pinfunction "1_1") (pintype "passive"))
      (node (ref "U$3") (pin "P$1") (pinfunction "2_P$1") (pintype "passive"))
    )
    (net (code "58") (name "Net-(U$3-3)") (class "Default")
      (node (ref "JP7") (pin "2") (pinfunction "2_2") (pintype "passive"))
      (node (ref "U$3") (pin "P$2") (pinfunction "3_P$2") (pintype "passive"))
    )
    (net (code "59") (name "Net-(U$4-2)") (class "Default")
      (node (ref "R14") (pin "2") (pinfunction "2_2") (pintype "passive"))
      (node (ref "U$4") (pin "P$1") (pinfunction "2_P$1") (pintype "passive"))
    )
    (net (code "60") (name "Net-(U$4-3)") (class "Default")
      (node (ref "R30") (pin "2") (pinfunction "2_2") (pintype "passive"))
      (node (ref "U$4") (pin "P$2") (pinfunction "3_P$2") (pintype "passive"))
    )
    (net (code "61") (name "Net-(U$5-2)") (class "Default")
      (node (ref "R24") (pin "1") (pinfunction "1_1") (pintype "passive"))
      (node (ref "U$5") (pin "P$1") (pinfunction "2_P$1") (pintype "passive"))
    )
    (net (code "62") (name "Net-(U$5-3)") (class "Default")
      (node (ref "JP8") (pin "2") (pinfunction "2_2") (pintype "passive"))
      (node (ref "U$5") (pin "P$2") (pinfunction "3_P$2") (pintype "passive"))
    )
    (net (code "63") (name "Net-(U$6-2)") (class "Default")
      (node (ref "R25") (pin "2") (pinfunction "2_2") (pintype "passive"))
      (node (ref "U$6") (pin "P$1") (pinfunction "2_P$1") (pintype "passive"))
    )
    (net (code "64") (name "Net-(U$6-3)") (class "Default")
      (node (ref "R41") (pin "2") (pinfunction "2_2") (pintype "passive"))
      (node (ref "U$6") (pin "P$2") (pinfunction "3_P$2") (pintype "passive"))
    )
    (net (code "65") (name "Net-(U$7-2)") (class "Default")
      (node (ref "R35") (pin "1") (pinfunction "1_1") (pintype "passive"))
      (node (ref "U$7") (pin "P$1") (pinfunction "2_P$1") (pintype "passive"))
    )
    (net (code "66") (name "Net-(U$7-3)") (class "Default")
      (node (ref "JP9") (pin "2") (pinfunction "2_2") (pintype "passive"))
      (node (ref "U$7") (pin "P$2") (pinfunction "3_P$2") (pintype "passive"))
    )
    (net (code "67") (name "Net-(U$8-2)") (class "Default")
      (node (ref "R36") (pin "2") (pinfunction "2_2") (pintype "passive"))
      (node (ref "U$8") (pin "P$1") (pinfunction "2_P$1") (pintype "passive"))
    )
    (net (code "68") (name "V+") (class "Default")
      (node (ref "C10") (pin "1") (pinfunction "1_1") (pintype "passive"))
      (node (ref "C11") (pin "1") (pinfunction "1_1") (pintype "passive"))
      (node (ref "C16") (pin "+") (pinfunction "+_+") (pintype "passive"))
      (node (ref "C6") (pin "1") (pinfunction "1_1") (pintype "passive"))
      (node (ref "C8") (pin "1") (pinfunction "1_1") (pintype "passive"))
      (node (ref "C9") (pin "1") (pinfunction "1_1") (pintype "passive"))
      (node (ref "D3") (pin "C") (pinfunction "C_C") (pintype "passive"))
      (node (ref "R8") (pin "2") (pinfunction "2_2") (pintype "passive"))
    )
    (net (code "69") (name "V-") (class "Default")
      (node (ref "C12") (pin "2") (pinfunction "2_2") (pintype "passive"))
      (node (ref "C13") (pin "2") (pinfunction "2_2") (pintype "passive"))
      (node (ref "C14") (pin "2") (pinfunction "2_2") (pintype "passive"))
      (node (ref "C15") (pin "2") (pinfunction "2_2") (pintype "passive"))
      (node (ref "C17") (pin "-") (pinfunction "-_-") (pintype "passive"))
      (node (ref "C7") (pin "2") (pinfunction "2_2") (pintype "passive"))
      (node (ref "D4") (pin "A") (pinfunction "A_A") (pintype "passive"))
    )
    (net (code "70") (name "unconnected-(U$8-3-PadP$2)") (class "Default")
      (node (ref "U$8") (pin "P$2") (pinfunction "3_P$2") (pintype "passive"))
    )
  )
)
